# CT_switch.net
KiCad netlist of a schematic drawn in Altium Designer
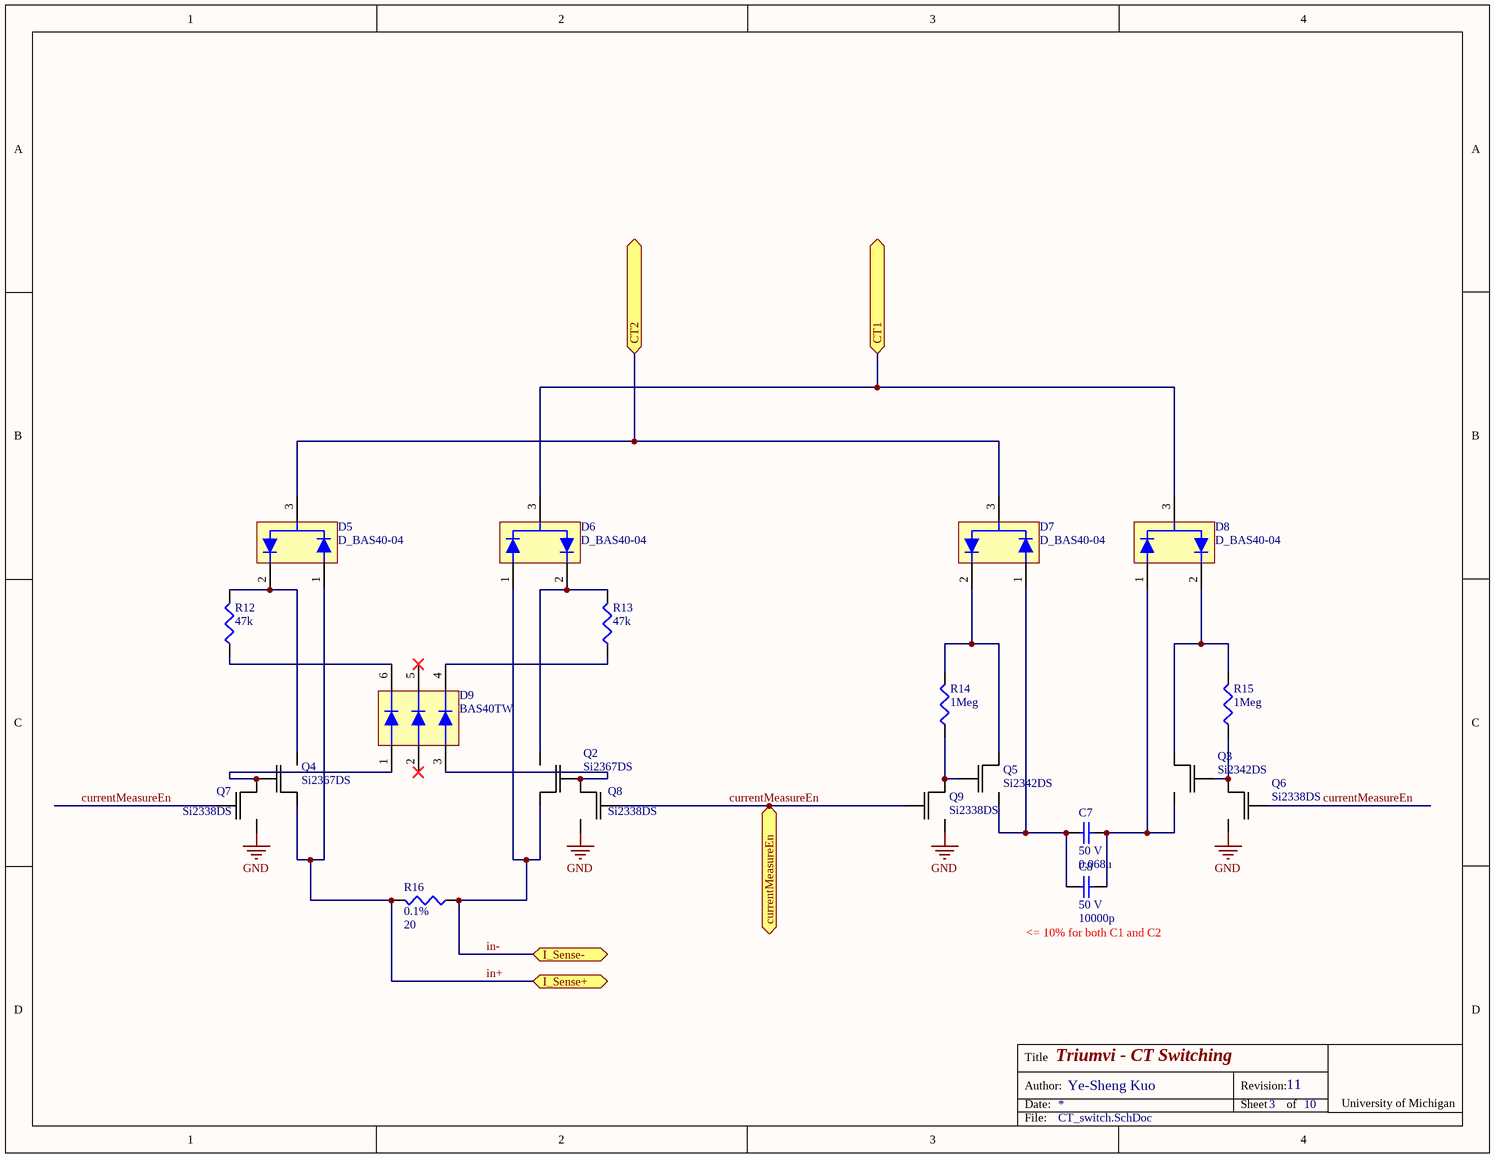
[diagram p0: CT_switch.SchDoc]

(export (version "E")
  (design (tool "Eeschema 10.0.6"))
  (components
    (comp (ref "C7")
      (value "0.068u")
      (footprint "0603")
      (description "0.068µF ±10% 50V Ceramic Capacitor X7R 0603")
      (fields
        (field (name "TOLERANCE") "10%")
        (field (name "VOLTAGE RATED") "50 V")
        (field (name "MANUFACTURER PART NUMBER") "C0603C683K5RACTU")
      )
      (libsource (lib "capacitors") (part "C0603C683K5RACTU"))
    )
    (comp (ref "C8")
      (value "10000p")
      (footprint "0603")
      (description "10000pF ±5% 50V Ceramic Capacitor X7R 0603")
      (fields
        (field (name "TOLERANCE") "5%")
        (field (name "VOLTAGE RATED") "50 V")
        (field (name "MANUFACTURER PART NUMBER") "C0603C103J5RACTU")
      )
      (libsource (lib "capacitors") (part "C0603C103J5RACTU"))
    )
    (comp (ref "D5")
      (value "D_BAS40-04")
      (footprint "SOT23-3")
      (description "SURFACE MOUNT SCHOTTKY BARRIER DIODE")
      (libsource (lib "diodes") (part "D_BAS40-04"))
    )
    (comp (ref "D6")
      (value "D_BAS40-04")
      (footprint "SOT23-3")
      (description "SURFACE MOUNT SCHOTTKY BARRIER DIODE")
      (libsource (lib "") (part "D_BAS40-04_1"))
    )
    (comp (ref "D7")
      (value "D_BAS40-04")
      (footprint "SOT23-3")
      (description "SURFACE MOUNT SCHOTTKY BARRIER DIODE")
      (libsource (lib "diodes") (part "D_BAS40-04"))
    )
    (comp (ref "D8")
      (value "D_BAS40-04")
      (footprint "SOT23-3")
      (description "SURFACE MOUNT SCHOTTKY BARRIER DIODE")
      (libsource (lib "") (part "D_BAS40-04_1"))
    )
    (comp (ref "D9")
      (value "BAS40TW")
      (footprint "SOT-363")
      (description "SURFACE MOUNT SCHOTTKY BARRIER DIODE ARRAYS")
      (libsource (lib "diodes") (part "D_BAS40TW"))
    )
    (comp (ref "Q2")
      (value "Si2367DS")
      (footprint "SOT23-3")
      (description "P-Channel 20 V (D-S) MOSFET")
      (libsource (lib "transistors") (part "Si2367DS"))
    )
    (comp (ref "Q3")
      (value "Si2342DS")
      (footprint "SOT23-3")
      (description "N-Channel 8 V (D-S) MOSFET")
      (libsource (lib "transistors") (part "Si2342DS"))
    )
    (comp (ref "Q4")
      (value "Si2367DS")
      (footprint "SOT23-3")
      (description "P-Channel 20 V (D-S) MOSFET")
      (libsource (lib "transistors") (part "Si2367DS"))
    )
    (comp (ref "Q5")
      (value "Si2342DS")
      (footprint "SOT23-3")
      (description "N-Channel 8 V (D-S) MOSFET")
      (libsource (lib "transistors") (part "Si2342DS"))
    )
    (comp (ref "Q6")
      (value "Si2338DS")
      (footprint "SOT23-3")
      (description "N-Channel 30 V (D-S) MOSFET")
      (libsource (lib "transistors") (part "Si2338DS"))
    )
    (comp (ref "Q7")
      (value "Si2338DS")
      (footprint "SOT23-3")
      (description "N-Channel 30 V (D-S) MOSFET")
      (libsource (lib "transistors") (part "Si2338DS"))
    )
    (comp (ref "Q8")
      (value "Si2338DS")
      (footprint "SOT23-3")
      (description "N-Channel 30 V (D-S) MOSFET")
      (libsource (lib "transistors") (part "Si2338DS"))
    )
    (comp (ref "Q9")
      (value "Si2338DS")
      (footprint "SOT23-3")
      (description "N-Channel 30 V (D-S) MOSFET")
      (libsource (lib "transistors") (part "Si2338DS"))
    )
    (comp (ref "R12")
      (value "47k")
      (footprint "0402")
      (description "RES SMD 47K OHM 1% 1/16W 0402")
      (fields (field (name "TOLERANCE") "1%") (field (name "POWER") "1/16 W"))
      (libsource (lib "resistors") (part "CRCW040247K0FKED"))
    )
    (comp (ref "R13")
      (value "47k")
      (footprint "0402")
      (description "RES SMD 47K OHM 1% 1/16W 0402")
      (fields (field (name "TOLERANCE") "1%") (field (name "POWER") "1/16 W"))
      (libsource (lib "resistors") (part "CRCW040247K0FKED"))
    )
    (comp (ref "R14")
      (value "1Meg")
      (footprint "0402")
      (description "RES SMD 1M OHM 1% 1/16W 0402")
      (fields (field (name "TOLERANCE") "1%") (field (name "POWER") "1/16 W"))
      (libsource (lib "resistors") (part "CRCW04021M00FKED"))
    )
    (comp (ref "R15")
      (value "1Meg")
      (footprint "0402")
      (description "RES SMD 1M OHM 1% 1/16W 0402")
      (fields (field (name "TOLERANCE") "1%") (field (name "POWER") "1/16 W"))
      (libsource (lib "resistors") (part "CRCW04021M00FKED"))
    )
    (comp (ref "R16")
      (value "20")
      (footprint "0805")
      (description "RES SMD 20 OHM 0.1% 1/5W 0805")
      (fields
        (field (name "MANUFACTURER PART NUMBER") "RTAN0805BKE20R0")
        (field (name "MANUFACTURER") "Stackpole Electronics Inc.")
        (field (name "TOLERANCE") "0.1%")
      )
      (libsource (lib "resistors") (part "RTAN0805BKE20R0"))
    )
  )
  (nets
    (net (code "1") (name "/CT1") (class "Default")
      (node (ref "D6") (pin "3") (pinfunction "3_3") (pintype "passive"))
      (node (ref "D8") (pin "3") (pinfunction "3_3") (pintype "passive"))
    )
    (net (code "2") (name "/CT2") (class "Default")
      (node (ref "D5") (pin "3") (pinfunction "3_3") (pintype "passive"))
      (node (ref "D7") (pin "3") (pinfunction "3_3") (pintype "passive"))
    )
    (net (code "3") (name "/currentMeasureEn") (class "Default")
      (node (ref "Q6") (pin "1") (pinfunction "G_1") (pintype "passive"))
      (node (ref "Q7") (pin "1") (pinfunction "G_1") (pintype "passive"))
      (node (ref "Q8") (pin "1") (pinfunction "G_1") (pintype "passive"))
      (node (ref "Q9") (pin "1") (pinfunction "G_1") (pintype "passive"))
    )
    (net (code "4") (name "/in+") (class "Default")
      (node (ref "D5") (pin "1") (pinfunction "1_1") (pintype "passive"))
      (node (ref "Q4") (pin "3") (pinfunction "D_3") (pintype "passive"))
      (node (ref "R16") (pin "1") (pintype "passive"))
    )
    (net (code "5") (name "/in-") (class "Default")
      (node (ref "D6") (pin "1") (pinfunction "1_1") (pintype "passive"))
      (node (ref "Q2") (pin "3") (pinfunction "D_3") (pintype "passive"))
      (node (ref "R16") (pin "2") (pintype "passive"))
    )
    (net (code "6") (name "GND") (class "Default")
      (node (ref "Q6") (pin "2") (pinfunction "S_2") (pintype "passive"))
      (node (ref "Q7") (pin "2") (pinfunction "S_2") (pintype "passive"))
      (node (ref "Q8") (pin "2") (pinfunction "S_2") (pintype "passive"))
      (node (ref "Q9") (pin "2") (pinfunction "S_2") (pintype "passive"))
    )
    (net (code "7") (name "Net-(D9-Pad4)") (class "Default")
      (node (ref "D9") (pin "4") (pinfunction "4_4") (pintype "passive"))
      (node (ref "R13") (pin "2") (pintype "passive"))
    )
    (net (code "8") (name "Net-(D9-Pad6)") (class "Default")
      (node (ref "D9") (pin "6") (pinfunction "6_6") (pintype "passive"))
      (node (ref "R12") (pin "2") (pintype "passive"))
    )
    (net (code "9") (name "Net-(Q2-G)") (class "Default")
      (node (ref "D9") (pin "3") (pinfunction "3_3") (pintype "passive"))
      (node (ref "Q2") (pin "1") (pinfunction "G_1") (pintype "passive"))
      (node (ref "Q8") (pin "3") (pinfunction "D_3") (pintype "passive"))
    )
    (net (code "10") (name "Net-(Q2-S)") (class "Default")
      (node (ref "D6") (pin "2") (pinfunction "2_2") (pintype "passive"))
      (node (ref "Q2") (pin "2") (pinfunction "S_2") (pintype "passive"))
      (node (ref "R13") (pin "1") (pintype "passive"))
    )
    (net (code "11") (name "Net-(Q3-D)") (class "Default")
      (node (ref "D8") (pin "2") (pinfunction "2_2") (pintype "passive"))
      (node (ref "Q3") (pin "3") (pinfunction "D_3") (pintype "passive"))
      (node (ref "R15") (pin "1") (pintype "passive"))
    )
    (net (code "12") (name "Net-(Q3-G)") (class "Default")
      (node (ref "Q3") (pin "1") (pinfunction "G_1") (pintype "passive"))
      (node (ref "Q6") (pin "3") (pinfunction "D_3") (pintype "passive"))
      (node (ref "R15") (pin "2") (pintype "passive"))
    )
    (net (code "13") (name "Net-(Q3-S)") (class "Default")
      (node (ref "C7") (pin "2") (pintype "passive"))
      (node (ref "C8") (pin "2") (pintype "passive"))
      (node (ref "D8") (pin "1") (pinfunction "1_1") (pintype "passive"))
      (node (ref "Q3") (pin "2") (pinfunction "S_2") (pintype "passive"))
    )
    (net (code "14") (name "Net-(Q4-G)") (class "Default")
      (node (ref "D9") (pin "1") (pinfunction "1_1") (pintype "passive"))
      (node (ref "Q4") (pin "1") (pinfunction "G_1") (pintype "passive"))
      (node (ref "Q7") (pin "3") (pinfunction "D_3") (pintype "passive"))
    )
    (net (code "15") (name "Net-(Q4-S)") (class "Default")
      (node (ref "D5") (pin "2") (pinfunction "2_2") (pintype "passive"))
      (node (ref "Q4") (pin "2") (pinfunction "S_2") (pintype "passive"))
      (node (ref "R12") (pin "1") (pintype "passive"))
    )
    (net (code "16") (name "Net-(Q5-D)") (class "Default")
      (node (ref "D7") (pin "2") (pinfunction "2_2") (pintype "passive"))
      (node (ref "Q5") (pin "3") (pinfunction "D_3") (pintype "passive"))
      (node (ref "R14") (pin "1") (pintype "passive"))
    )
    (net (code "17") (name "Net-(Q5-G)") (class "Default")
      (node (ref "Q5") (pin "1") (pinfunction "G_1") (pintype "passive"))
      (node (ref "Q9") (pin "3") (pinfunction "D_3") (pintype "passive"))
      (node (ref "R14") (pin "2") (pintype "passive"))
    )
    (net (code "18") (name "Net-(Q5-S)") (class "Default")
      (node (ref "C7") (pin "1") (pintype "passive"))
      (node (ref "C8") (pin "1") (pintype "passive"))
      (node (ref "D7") (pin "1") (pinfunction "1_1") (pintype "passive"))
      (node (ref "Q5") (pin "2") (pinfunction "S_2") (pintype "passive"))
    )
    (net (code "19") (name "unconnected-(D9-Pad2)") (class "Default")
      (node (ref "D9") (pin "2") (pinfunction "2_2") (pintype "passive+no_connect"))
    )
    (net (code "20") (name "unconnected-(D9-Pad5)") (class "Default")
      (node (ref "D9") (pin "5") (pinfunction "5_5") (pintype "passive+no_connect"))
    )
  )
)
